# led-taster_4te_v0_01.net
KiCad netlist of a schematic drawn in EAGLE
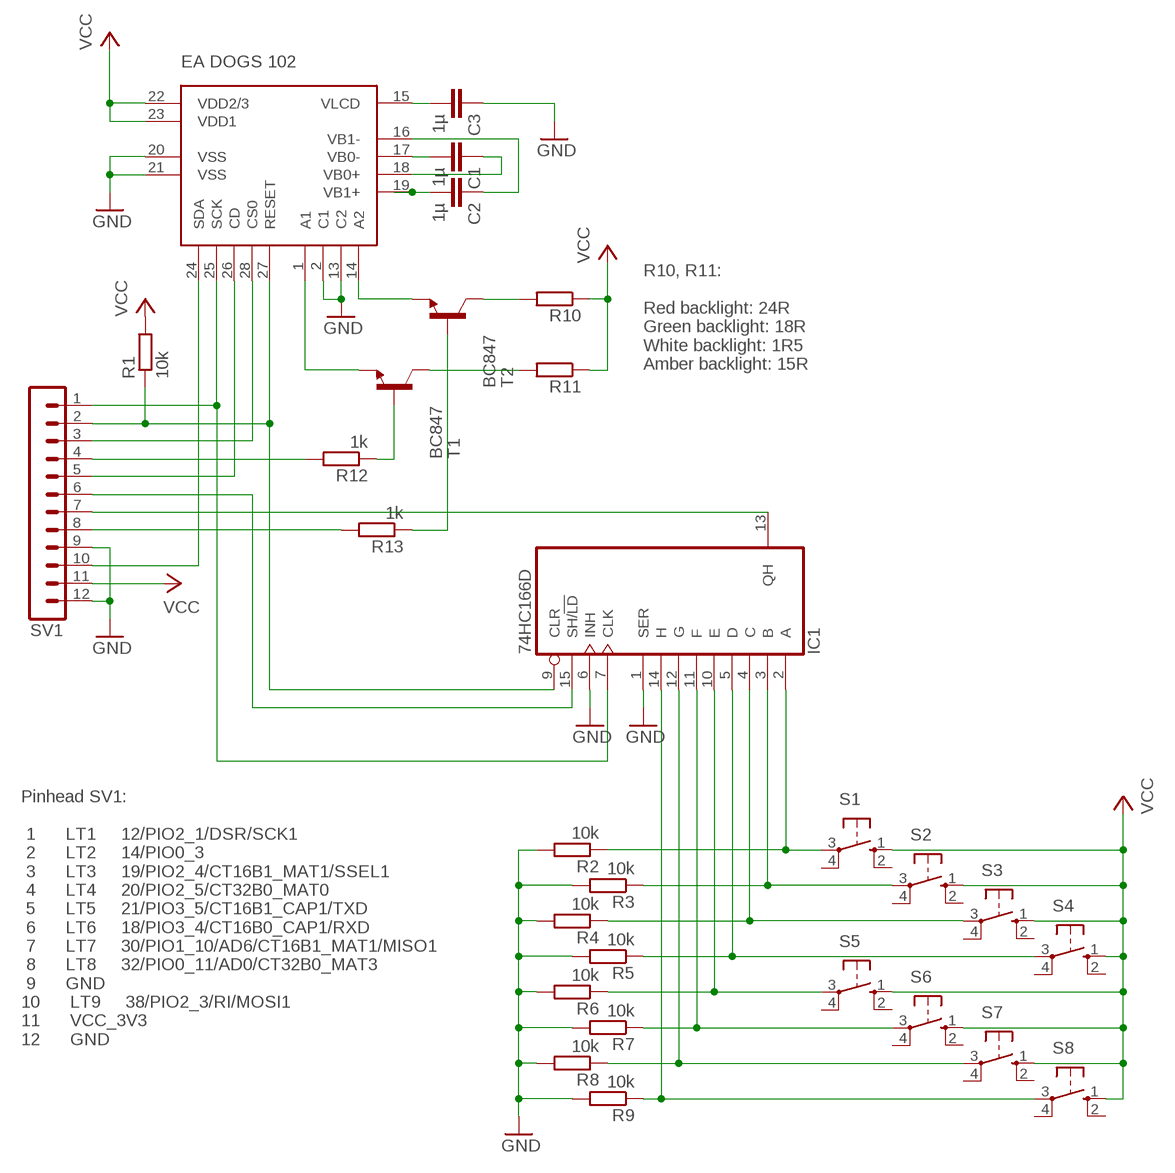
[diagram p0: schematic, sheet 1]

(export (version "E")
  (design (tool "Eeschema 10.0.6"))
  (components
    (comp (ref "C1")
      (value "1µ")
      (footprint "eagle-import:C1210")
      (libsource (lib "eagle-import") (part "C-EUC1210"))
    )
    (comp (ref "C2")
      (value "1µ")
      (footprint "eagle-import:C1210")
      (libsource (lib "eagle-import") (part "C-EUC1210"))
    )
    (comp (ref "C3")
      (value "1µ")
      (footprint "eagle-import:C1210")
      (libsource (lib "eagle-import") (part "C-EUC1210"))
    )
    (comp (ref "EA_DOGS102")
      (value "DOGS102")
      (footprint "eagle-import:DOGS102")
      (libsource (lib "eagle-import") (part "DOGS102"))
    )
    (comp (ref "IC1")
      (value "74HC166D")
      (footprint "eagle-import:SO16")
      (libsource (lib "eagle-import") (part "74166DHC"))
    )
    (comp (ref "R1")
      (value "10k")
      (footprint "eagle-import:R1206")
      (libsource (lib "eagle-import") (part "R-EU_R1206"))
    )
    (comp (ref "R2")
      (value "10k")
      (footprint "eagle-import:R1206")
      (libsource (lib "eagle-import") (part "R-EU_R1206"))
    )
    (comp (ref "R3")
      (value "10k")
      (footprint "eagle-import:R1206")
      (libsource (lib "eagle-import") (part "R-EU_R1206"))
    )
    (comp (ref "R4")
      (value "10k")
      (footprint "eagle-import:R1206")
      (libsource (lib "eagle-import") (part "R-EU_R1206"))
    )
    (comp (ref "R5")
      (value "10k")
      (footprint "eagle-import:R1206")
      (libsource (lib "eagle-import") (part "R-EU_R1206"))
    )
    (comp (ref "R6")
      (value "10k")
      (footprint "eagle-import:R1206")
      (libsource (lib "eagle-import") (part "R-EU_R1206"))
    )
    (comp (ref "R7")
      (value "10k")
      (footprint "eagle-import:R1206")
      (libsource (lib "eagle-import") (part "R-EU_R1206"))
    )
    (comp (ref "R8")
      (value "10k")
      (footprint "eagle-import:R1206")
      (libsource (lib "eagle-import") (part "R-EU_R1206"))
    )
    (comp (ref "R9")
      (value "10k")
      (footprint "eagle-import:R1206")
      (libsource (lib "eagle-import") (part "R-EU_R1206"))
    )
    (comp (ref "R10")
      (value "R-EU_R1206")
      (footprint "eagle-import:R1206")
      (libsource (lib "eagle-import") (part "R-EU_R1206"))
    )
    (comp (ref "R11")
      (value "R-EU_R1206")
      (footprint "eagle-import:R1206")
      (libsource (lib "eagle-import") (part "R-EU_R1206"))
    )
    (comp (ref "R12")
      (value "1k")
      (footprint "eagle-import:R1206")
      (libsource (lib "eagle-import") (part "R-EU_R1206"))
    )
    (comp (ref "R13")
      (value "1k")
      (footprint "eagle-import:R1206")
      (libsource (lib "eagle-import") (part "R-EU_R1206"))
    )
    (comp (ref "S1")
      (value "10-XX")
      (footprint "eagle-import:B3F-10XX")
      (fields (field (name "MPN") "B3F-1000"))
      (libsource (lib "eagle-import") (part "10-XX"))
    )
    (comp (ref "S2")
      (value "10-XX")
      (footprint "eagle-import:B3F-10XX")
      (fields (field (name "MPN") "B3F-1000"))
      (libsource (lib "eagle-import") (part "10-XX"))
    )
    (comp (ref "S3")
      (value "10-XX")
      (footprint "eagle-import:B3F-10XX")
      (fields (field (name "MPN") "B3F-1000"))
      (libsource (lib "eagle-import") (part "10-XX"))
    )
    (comp (ref "S4")
      (value "10-XX")
      (footprint "eagle-import:B3F-10XX")
      (fields (field (name "MPN") "B3F-1000"))
      (libsource (lib "eagle-import") (part "10-XX"))
    )
    (comp (ref "S5")
      (value "10-XX")
      (footprint "eagle-import:B3F-10XX")
      (fields (field (name "MPN") "B3F-1000"))
      (libsource (lib "eagle-import") (part "10-XX"))
    )
    (comp (ref "S6")
      (value "10-XX")
      (footprint "eagle-import:B3F-10XX")
      (fields (field (name "MPN") "B3F-1000"))
      (libsource (lib "eagle-import") (part "10-XX"))
    )
    (comp (ref "S7")
      (value "10-XX")
      (footprint "eagle-import:B3F-10XX")
      (fields (field (name "MPN") "B3F-1000"))
      (libsource (lib "eagle-import") (part "10-XX"))
    )
    (comp (ref "S8")
      (value "10-XX")
      (footprint "eagle-import:B3F-10XX")
      (fields (field (name "MPN") "B3F-1000"))
      (libsource (lib "eagle-import") (part "10-XX"))
    )
    (comp (ref "SV1")
      (value "MA12-1")
      (footprint "eagle-import:MA12-1")
      (libsource (lib "eagle-import") (part "MA12-1"))
    )
    (comp (ref "T1")
      (value "BC847")
      (footprint "eagle-import:SOT23")
      (libsource (lib "eagle-import") (part "BC847"))
    )
    (comp (ref "T2")
      (value "BC847")
      (footprint "eagle-import:SOT23")
      (libsource (lib "eagle-import") (part "BC847"))
    )
  )
  (nets
    (net (code "1") (name "GND") (class "Default")
      (node (ref "C3") (pin "1") (pinfunction "1_1") (pintype "passive"))
      (node (ref "EA_DOGS102") (pin "13") (pinfunction "C2_13") (pintype "bidirectional"))
      (node (ref "EA_DOGS102") (pin "2") (pinfunction "C1_2") (pintype "bidirectional"))
      (node (ref "EA_DOGS102") (pin "20") (pinfunction "VSS_20") (pintype "power_in"))
      (node (ref "EA_DOGS102") (pin "21") (pinfunction "VSS_21") (pintype "power_in"))
      (node (ref "IC1") (pin "1") (pinfunction "SER_1") (pintype "input"))
      (node (ref "IC1") (pin "6") (pinfunction "INH_6") (pintype "input"))
      (node (ref "R2") (pin "2") (pinfunction "2_2") (pintype "passive"))
      (node (ref "R3") (pin "2") (pinfunction "2_2") (pintype "passive"))
      (node (ref "R4") (pin "2") (pinfunction "2_2") (pintype "passive"))
      (node (ref "R5") (pin "2") (pinfunction "2_2") (pintype "passive"))
      (node (ref "R6") (pin "2") (pinfunction "2_2") (pintype "passive"))
      (node (ref "R7") (pin "2") (pinfunction "2_2") (pintype "passive"))
      (node (ref "R8") (pin "2") (pinfunction "2_2") (pintype "passive"))
      (node (ref "R9") (pin "2") (pinfunction "2_2") (pintype "passive"))
      (node (ref "SV1") (pin "12") (pinfunction "12_12") (pintype "passive"))
      (node (ref "SV1") (pin "9") (pinfunction "9_9") (pintype "passive"))
    )
    (net (code "2") (name "Net-(EA_DOGS102-A1)") (class "Default")
      (node (ref "EA_DOGS102") (pin "1") (pinfunction "A1_1") (pintype "bidirectional"))
      (node (ref "T1") (pin "2") (pinfunction "E_2") (pintype "passive"))
    )
    (net (code "3") (name "Net-(EA_DOGS102-A2)") (class "Default")
      (node (ref "EA_DOGS102") (pin "14") (pinfunction "A2_14") (pintype "bidirectional"))
      (node (ref "T2") (pin "2") (pinfunction "E_2") (pintype "passive"))
    )
    (net (code "4") (name "Net-(EA_DOGS102-CD)") (class "Default")
      (node (ref "EA_DOGS102") (pin "26") (pinfunction "CD_26") (pintype "bidirectional"))
      (node (ref "SV1") (pin "5") (pinfunction "5_5") (pintype "passive"))
    )
    (net (code "5") (name "Net-(EA_DOGS102-CS0)") (class "Default")
      (node (ref "EA_DOGS102") (pin "28") (pinfunction "CS0_28") (pintype "bidirectional"))
      (node (ref "SV1") (pin "3") (pinfunction "3_3") (pintype "passive"))
    )
    (net (code "6") (name "Net-(EA_DOGS102-RESET)") (class "Default")
      (node (ref "EA_DOGS102") (pin "27") (pinfunction "RESET_27") (pintype "bidirectional"))
      (node (ref "IC1") (pin "9") (pinfunction "CLR_9") (pintype "input"))
      (node (ref "R1") (pin "1") (pinfunction "1_1") (pintype "passive"))
      (node (ref "SV1") (pin "2") (pinfunction "2_2") (pintype "passive"))
    )
    (net (code "7") (name "Net-(EA_DOGS102-SCK)") (class "Default")
      (node (ref "EA_DOGS102") (pin "25") (pinfunction "SCK_25") (pintype "bidirectional"))
      (node (ref "IC1") (pin "7") (pinfunction "CLK_7") (pintype "input"))
      (node (ref "SV1") (pin "1") (pinfunction "1_1") (pintype "passive"))
    )
    (net (code "8") (name "Net-(EA_DOGS102-SDA)") (class "Default")
      (node (ref "EA_DOGS102") (pin "24") (pinfunction "SDA_24") (pintype "bidirectional"))
      (node (ref "SV1") (pin "10") (pinfunction "10_10") (pintype "passive"))
    )
    (net (code "9") (name "Net-(EA_DOGS102-VB0+)") (class "Default")
      (node (ref "C1") (pin "1") (pinfunction "1_1") (pintype "passive"))
      (node (ref "EA_DOGS102") (pin "18") (pinfunction "VB0+_18") (pintype "bidirectional"))
    )
    (net (code "10") (name "Net-(EA_DOGS102-VB0-)") (class "Default")
      (node (ref "C1") (pin "2") (pinfunction "2_2") (pintype "passive"))
      (node (ref "EA_DOGS102") (pin "17") (pinfunction "VB0-_17") (pintype "bidirectional"))
    )
    (net (code "11") (name "Net-(EA_DOGS102-VB1+)") (class "Default")
      (node (ref "C2") (pin "2") (pinfunction "2_2") (pintype "passive"))
      (node (ref "EA_DOGS102") (pin "19") (pinfunction "VB1+_19") (pintype "bidirectional"))
    )
    (net (code "12") (name "Net-(EA_DOGS102-VB1-)") (class "Default")
      (node (ref "C2") (pin "1") (pinfunction "1_1") (pintype "passive"))
      (node (ref "EA_DOGS102") (pin "16") (pinfunction "VB1-_16") (pintype "bidirectional"))
    )
    (net (code "13") (name "Net-(EA_DOGS102-VLCD)") (class "Default")
      (node (ref "C3") (pin "2") (pinfunction "2_2") (pintype "passive"))
      (node (ref "EA_DOGS102") (pin "15") (pinfunction "VLCD_15") (pintype "bidirectional"))
    )
    (net (code "14") (name "Net-(IC1A-A)") (class "Default")
      (node (ref "IC1") (pin "2") (pinfunction "A_2") (pintype "input"))
      (node (ref "R2") (pin "1") (pinfunction "1_1") (pintype "passive"))
      (node (ref "S1") (pin "3") (pinfunction "P_3") (pintype "passive"))
    )
    (net (code "15") (name "Net-(IC1A-B)") (class "Default")
      (node (ref "IC1") (pin "3") (pinfunction "B_3") (pintype "input"))
      (node (ref "R3") (pin "1") (pinfunction "1_1") (pintype "passive"))
      (node (ref "S2") (pin "3") (pinfunction "P_3") (pintype "passive"))
    )
    (net (code "16") (name "Net-(IC1A-C)") (class "Default")
      (node (ref "IC1") (pin "4") (pinfunction "C_4") (pintype "input"))
      (node (ref "R4") (pin "1") (pinfunction "1_1") (pintype "passive"))
      (node (ref "S3") (pin "3") (pinfunction "P_3") (pintype "passive"))
    )
    (net (code "17") (name "Net-(IC1A-D)") (class "Default")
      (node (ref "IC1") (pin "5") (pinfunction "D_5") (pintype "input"))
      (node (ref "R5") (pin "1") (pinfunction "1_1") (pintype "passive"))
      (node (ref "S4") (pin "3") (pinfunction "P_3") (pintype "passive"))
    )
    (net (code "18") (name "Net-(IC1A-E)") (class "Default")
      (node (ref "IC1") (pin "10") (pinfunction "E_10") (pintype "input"))
      (node (ref "R6") (pin "1") (pinfunction "1_1") (pintype "passive"))
      (node (ref "S5") (pin "3") (pinfunction "P_3") (pintype "passive"))
    )
    (net (code "19") (name "Net-(IC1A-F)") (class "Default")
      (node (ref "IC1") (pin "11") (pinfunction "F_11") (pintype "input"))
      (node (ref "R7") (pin "1") (pinfunction "1_1") (pintype "passive"))
      (node (ref "S6") (pin "3") (pinfunction "P_3") (pintype "passive"))
    )
    (net (code "20") (name "Net-(IC1A-G)") (class "Default")
      (node (ref "IC1") (pin "12") (pinfunction "G_12") (pintype "input"))
      (node (ref "R8") (pin "1") (pinfunction "1_1") (pintype "passive"))
      (node (ref "S7") (pin "3") (pinfunction "P_3") (pintype "passive"))
    )
    (net (code "21") (name "Net-(IC1A-H)") (class "Default")
      (node (ref "IC1") (pin "14") (pinfunction "H_14") (pintype "input"))
      (node (ref "R9") (pin "1") (pinfunction "1_1") (pintype "passive"))
      (node (ref "S8") (pin "3") (pinfunction "P_3") (pintype "passive"))
    )
    (net (code "22") (name "Net-(IC1A-QH)") (class "Default")
      (node (ref "IC1") (pin "13") (pinfunction "QH_13") (pintype "output"))
      (node (ref "SV1") (pin "7") (pinfunction "7_7") (pintype "passive"))
    )
    (net (code "23") (name "Net-(IC1A-SH{slash}~{LD})") (class "Default")
      (node (ref "IC1") (pin "15") (pinfunction "SH/~{LD}_15") (pintype "input"))
      (node (ref "SV1") (pin "6") (pinfunction "6_6") (pintype "passive"))
    )
    (net (code "24") (name "Net-(R12-Pad2)") (class "Default")
      (node (ref "R12") (pin "2") (pinfunction "2_2") (pintype "passive"))
      (node (ref "SV1") (pin "4") (pinfunction "4_4") (pintype "passive"))
    )
    (net (code "25") (name "Net-(R13-Pad2)") (class "Default")
      (node (ref "R13") (pin "2") (pinfunction "2_2") (pintype "passive"))
      (node (ref "SV1") (pin "8") (pinfunction "8_8") (pintype "passive"))
    )
    (net (code "26") (name "Net-(T1-B)") (class "Default")
      (node (ref "R12") (pin "1") (pinfunction "1_1") (pintype "passive"))
      (node (ref "T1") (pin "1") (pinfunction "B_1") (pintype "passive"))
    )
    (net (code "27") (name "Net-(T1-C)") (class "Default")
      (node (ref "R11") (pin "2") (pinfunction "2_2") (pintype "passive"))
      (node (ref "T1") (pin "3") (pinfunction "C_3") (pintype "passive"))
    )
    (net (code "28") (name "Net-(T2-B)") (class "Default")
      (node (ref "R13") (pin "1") (pinfunction "1_1") (pintype "passive"))
      (node (ref "T2") (pin "1") (pinfunction "B_1") (pintype "passive"))
    )
    (net (code "29") (name "Net-(T2-C)") (class "Default")
      (node (ref "R10") (pin "2") (pinfunction "2_2") (pintype "passive"))
      (node (ref "T2") (pin "3") (pinfunction "C_3") (pintype "passive"))
    )
    (net (code "30") (name "VCC") (class "Default")
      (node (ref "EA_DOGS102") (pin "22") (pinfunction "VDD2/3_22") (pintype "power_in"))
      (node (ref "EA_DOGS102") (pin "23") (pinfunction "VDD1_23") (pintype "power_in"))
      (node (ref "R1") (pin "2") (pinfunction "2_2") (pintype "passive"))
      (node (ref "R10") (pin "1") (pinfunction "1_1") (pintype "passive"))
      (node (ref "R11") (pin "1") (pinfunction "1_1") (pintype "passive"))
      (node (ref "S1") (pin "1") (pinfunction "S_1") (pintype "passive"))
      (node (ref "S2") (pin "1") (pinfunction "S_1") (pintype "passive"))
      (node (ref "S3") (pin "1") (pinfunction "S_1") (pintype "passive"))
      (node (ref "S4") (pin "1") (pinfunction "S_1") (pintype "passive"))
      (node (ref "S5") (pin "1") (pinfunction "S_1") (pintype "passive"))
      (node (ref "S6") (pin "1") (pinfunction "S_1") (pintype "passive"))
      (node (ref "S7") (pin "1") (pinfunction "S_1") (pintype "passive"))
      (node (ref "S8") (pin "1") (pinfunction "S_1") (pintype "passive"))
      (node (ref "SV1") (pin "11") (pinfunction "11_11") (pintype "passive"))
    )
    (net (code "31") (name "unconnected-(S1-P1-Pad4)") (class "Default")
      (node (ref "S1") (pin "4") (pinfunction "P1_4") (pintype "passive"))
    )
    (net (code "32") (name "unconnected-(S1-S1-Pad2)") (class "Default")
      (node (ref "S1") (pin "2") (pinfunction "S1_2") (pintype "passive"))
    )
    (net (code "33") (name "unconnected-(S2-P1-Pad4)") (class "Default")
      (node (ref "S2") (pin "4") (pinfunction "P1_4") (pintype "passive"))
    )
    (net (code "34") (name "unconnected-(S2-S1-Pad2)") (class "Default")
      (node (ref "S2") (pin "2") (pinfunction "S1_2") (pintype "passive"))
    )
    (net (code "35") (name "unconnected-(S3-P1-Pad4)") (class "Default")
      (node (ref "S3") (pin "4") (pinfunction "P1_4") (pintype "passive"))
    )
    (net (code "36") (name "unconnected-(S3-S1-Pad2)") (class "Default")
      (node (ref "S3") (pin "2") (pinfunction "S1_2") (pintype "passive"))
    )
    (net (code "37") (name "unconnected-(S4-P1-Pad4)") (class "Default")
      (node (ref "S4") (pin "4") (pinfunction "P1_4") (pintype "passive"))
    )
    (net (code "38") (name "unconnected-(S4-S1-Pad2)") (class "Default")
      (node (ref "S4") (pin "2") (pinfunction "S1_2") (pintype "passive"))
    )
    (net (code "39") (name "unconnected-(S5-P1-Pad4)") (class "Default")
      (node (ref "S5") (pin "4") (pinfunction "P1_4") (pintype "passive"))
    )
    (net (code "40") (name "unconnected-(S5-S1-Pad2)") (class "Default")
      (node (ref "S5") (pin "2") (pinfunction "S1_2") (pintype "passive"))
    )
    (net (code "41") (name "unconnected-(S6-P1-Pad4)") (class "Default")
      (node (ref "S6") (pin "4") (pinfunction "P1_4") (pintype "passive"))
    )
    (net (code "42") (name "unconnected-(S6-S1-Pad2)") (class "Default")
      (node (ref "S6") (pin "2") (pinfunction "S1_2") (pintype "passive"))
    )
    (net (code "43") (name "unconnected-(S7-P1-Pad4)") (class "Default")
      (node (ref "S7") (pin "4") (pinfunction "P1_4") (pintype "passive"))
    )
    (net (code "44") (name "unconnected-(S7-S1-Pad2)") (class "Default")
      (node (ref "S7") (pin "2") (pinfunction "S1_2") (pintype "passive"))
    )
    (net (code "45") (name "unconnected-(S8-P1-Pad4)") (class "Default")
      (node (ref "S8") (pin "4") (pinfunction "P1_4") (pintype "passive"))
    )
    (net (code "46") (name "unconnected-(S8-S1-Pad2)") (class "Default")
      (node (ref "S8") (pin "2") (pinfunction "S1_2") (pintype "passive"))
    )
  )
)
